# IR_repeater.net
KiCad netlist of a schematic drawn in EAGLE
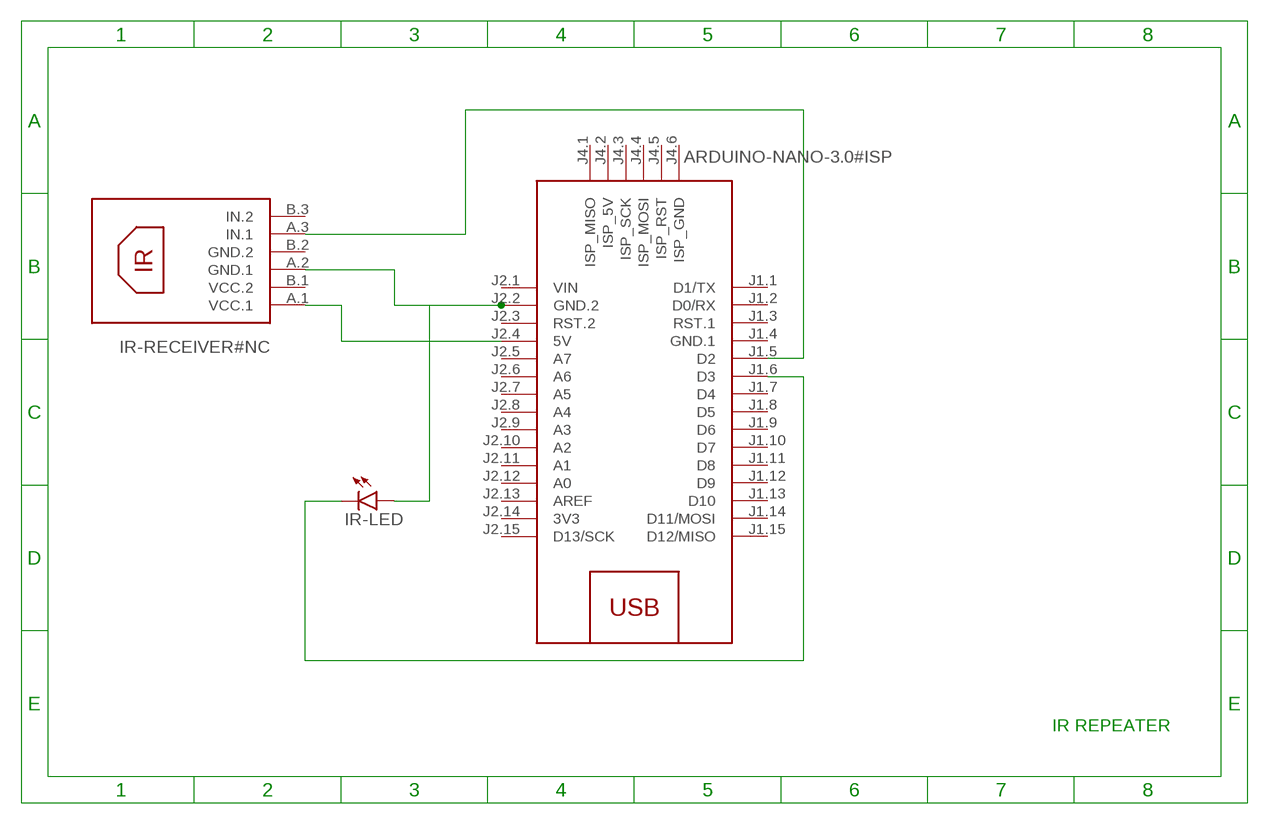
[diagram p0: schematic, sheet 1]

(export (version "E")
  (design (tool "Eeschema 10.0.6"))
  (components
    (comp (ref "IR-LED")
      (value "SFH482")
      (footprint "eagle-import:SFH482")
      (libsource (lib "eagle-import") (part "SFH482"))
    )
    (comp (ref "IR-RECEIVER")
      (value "IR-RECEIVER#NC")
      (footprint "eagle-import:IR-RECEIVER#NC")
      (libsource (lib "eagle-import") (part "IR-RECEIVER#NC"))
    )
    (comp (ref "M1")
      (value "ARDUINO-NANO-3.0#ISP")
      (footprint "eagle-import:ARDUINO-NANO-3.0#ISP")
      (libsource (lib "eagle-import") (part "ARDUINO-NANO-3.0#ISP"))
    )
  )
  (nets
    (net (code "1") (name "/3V3") (class "Default")
      (node (ref "M1") (pin "J2.14") (pinfunction "3V3_J2.14") (pintype "power_in"))
    )
    (net (code "2") (name "/GND.1") (class "Default")
      (node (ref "M1") (pin "J1.4") (pinfunction "GND.1_J1.4") (pintype "power_in"))
    )
    (net (code "3") (name "/VIN") (class "Default")
      (node (ref "M1") (pin "J2.1") (pinfunction "VIN_J2.1") (pintype "power_in"))
    )
    (net (code "4") (name "Net-(IR-LED-C)") (class "Default")
      (node (ref "IR-LED") (pin "K") (pinfunction "C_K") (pintype "passive"))
      (node (ref "M1") (pin "J1.6") (pinfunction "D3_J1.6") (pintype "bidirectional"))
    )
    (net (code "5") (name "Net-(IR-RECEIVER-GND.1)") (class "Default")
      (node (ref "IR-LED") (pin "A") (pinfunction "A_A") (pintype "passive"))
      (node (ref "IR-RECEIVER") (pin "A.2") (pinfunction "GND.1_A.2") (pintype "bidirectional"))
      (node (ref "M1") (pin "J2.2") (pinfunction "GND.2_J2.2") (pintype "power_in"))
    )
    (net (code "6") (name "Net-(IR-RECEIVER-IN.1)") (class "Default")
      (node (ref "IR-RECEIVER") (pin "A.3") (pinfunction "IN.1_A.3") (pintype "bidirectional"))
      (node (ref "M1") (pin "J1.5") (pinfunction "D2_J1.5") (pintype "bidirectional"))
    )
    (net (code "7") (name "Net-(IR-RECEIVER-VCC.1)") (class "Default")
      (node (ref "IR-RECEIVER") (pin "A.1") (pinfunction "VCC.1_A.1") (pintype "bidirectional"))
      (node (ref "M1") (pin "J2.4") (pinfunction "5V_J2.4") (pintype "power_in"))
    )
    (net (code "8") (name "unconnected-(IR-RECEIVER-GND.2-PadB.2)") (class "Default")
      (node (ref "IR-RECEIVER") (pin "B.2") (pinfunction "GND.2_B.2") (pintype "bidirectional"))
    )
    (net (code "9") (name "unconnected-(IR-RECEIVER-IN.2-PadB.3)") (class "Default")
      (node (ref "IR-RECEIVER") (pin "B.3") (pinfunction "IN.2_B.3") (pintype "bidirectional"))
    )
    (net (code "10") (name "unconnected-(IR-RECEIVER-VCC.2-PadB.1)") (class "Default")
      (node (ref "IR-RECEIVER") (pin "B.1") (pinfunction "VCC.2_B.1") (pintype "bidirectional"))
    )
    (net (code "11") (name "unconnected-(M1-A0-PadJ2.12)") (class "Default")
      (node (ref "M1") (pin "J2.12") (pinfunction "A0_J2.12") (pintype "bidirectional"))
    )
    (net (code "12") (name "unconnected-(M1-A1-PadJ2.11)") (class "Default")
      (node (ref "M1") (pin "J2.11") (pinfunction "A1_J2.11") (pintype "bidirectional"))
    )
    (net (code "13") (name "unconnected-(M1-A2-PadJ2.10)") (class "Default")
      (node (ref "M1") (pin "J2.10") (pinfunction "A2_J2.10") (pintype "bidirectional"))
    )
    (net (code "14") (name "unconnected-(M1-A3-PadJ2.9)") (class "Default")
      (node (ref "M1") (pin "J2.9") (pinfunction "A3_J2.9") (pintype "bidirectional"))
    )
    (net (code "15") (name "unconnected-(M1-A4-PadJ2.8)") (class "Default")
      (node (ref "M1") (pin "J2.8") (pinfunction "A4_J2.8") (pintype "bidirectional"))
    )
    (net (code "16") (name "unconnected-(M1-A5-PadJ2.7)") (class "Default")
      (node (ref "M1") (pin "J2.7") (pinfunction "A5_J2.7") (pintype "bidirectional"))
    )
    (net (code "17") (name "unconnected-(M1-A6-PadJ2.6)") (class "Default")
      (node (ref "M1") (pin "J2.6") (pinfunction "A6_J2.6") (pintype "bidirectional"))
    )
    (net (code "18") (name "unconnected-(M1-A7-PadJ2.5)") (class "Default")
      (node (ref "M1") (pin "J2.5") (pinfunction "A7_J2.5") (pintype "bidirectional"))
    )
    (net (code "19") (name "unconnected-(M1-AREF-PadJ2.13)") (class "Default")
      (node (ref "M1") (pin "J2.13") (pinfunction "AREF_J2.13") (pintype "bidirectional"))
    )
    (net (code "20") (name "unconnected-(M1-D0{slash}RX-PadJ1.2)") (class "Default")
      (node (ref "M1") (pin "J1.2") (pinfunction "D0/RX_J1.2") (pintype "bidirectional"))
    )
    (net (code "21") (name "unconnected-(M1-D1{slash}TX-PadJ1.1)") (class "Default")
      (node (ref "M1") (pin "J1.1") (pinfunction "D1/TX_J1.1") (pintype "bidirectional"))
    )
    (net (code "22") (name "unconnected-(M1-D4-PadJ1.7)") (class "Default")
      (node (ref "M1") (pin "J1.7") (pinfunction "D4_J1.7") (pintype "bidirectional"))
    )
    (net (code "23") (name "unconnected-(M1-D5-PadJ1.8)") (class "Default")
      (node (ref "M1") (pin "J1.8") (pinfunction "D5_J1.8") (pintype "bidirectional"))
    )
    (net (code "24") (name "unconnected-(M1-D6-PadJ1.9)") (class "Default")
      (node (ref "M1") (pin "J1.9") (pinfunction "D6_J1.9") (pintype "bidirectional"))
    )
    (net (code "25") (name "unconnected-(M1-D7-PadJ1.10)") (class "Default")
      (node (ref "M1") (pin "J1.10") (pinfunction "D7_J1.10") (pintype "bidirectional"))
    )
    (net (code "26") (name "unconnected-(M1-D8-PadJ1.11)") (class "Default")
      (node (ref "M1") (pin "J1.11") (pinfunction "D8_J1.11") (pintype "bidirectional"))
    )
    (net (code "27") (name "unconnected-(M1-D9-PadJ1.12)") (class "Default")
      (node (ref "M1") (pin "J1.12") (pinfunction "D9_J1.12") (pintype "bidirectional"))
    )
    (net (code "28") (name "unconnected-(M1-D10-PadJ1.13)") (class "Default")
      (node (ref "M1") (pin "J1.13") (pinfunction "D10_J1.13") (pintype "bidirectional"))
    )
    (net (code "29") (name "unconnected-(M1-D11{slash}MOSI-PadJ1.14)") (class "Default")
      (node (ref "M1") (pin "J1.14") (pinfunction "D11/MOSI_J1.14") (pintype "bidirectional"))
    )
    (net (code "30") (name "unconnected-(M1-D12{slash}MISO-PadJ1.15)") (class "Default")
      (node (ref "M1") (pin "J1.15") (pinfunction "D12/MISO_J1.15") (pintype "bidirectional"))
    )
    (net (code "31") (name "unconnected-(M1-D13{slash}SCK-PadJ2.15)") (class "Default")
      (node (ref "M1") (pin "J2.15") (pinfunction "D13/SCK_J2.15") (pintype "bidirectional"))
    )
    (net (code "32") (name "unconnected-(M1-ISP_5V-PadJ4.2)") (class "Default")
      (node (ref "M1") (pin "J4.2") (pinfunction "ISP_5V_J4.2") (pintype "bidirectional"))
    )
    (net (code "33") (name "unconnected-(M1-ISP_GND-PadJ4.6)") (class "Default")
      (node (ref "M1") (pin "J4.6") (pinfunction "ISP_GND_J4.6") (pintype "bidirectional"))
    )
    (net (code "34") (name "unconnected-(M1-ISP_MISO-PadJ4.1)") (class "Default")
      (node (ref "M1") (pin "J4.1") (pinfunction "ISP_MISO_J4.1") (pintype "bidirectional"))
    )
    (net (code "35") (name "unconnected-(M1-ISP_MOSI-PadJ4.4)") (class "Default")
      (node (ref "M1") (pin "J4.4") (pinfunction "ISP_MOSI_J4.4") (pintype "bidirectional"))
    )
    (net (code "36") (name "unconnected-(M1-ISP_RST-PadJ4.5)") (class "Default")
      (node (ref "M1") (pin "J4.5") (pinfunction "ISP_RST_J4.5") (pintype "bidirectional"))
    )
    (net (code "37") (name "unconnected-(M1-ISP_SCK-PadJ4.3)") (class "Default")
      (node (ref "M1") (pin "J4.3") (pinfunction "ISP_SCK_J4.3") (pintype "bidirectional"))
    )
    (net (code "38") (name "unconnected-(M1-RST.1-PadJ1.3)") (class "Default")
      (node (ref "M1") (pin "J1.3") (pinfunction "RST.1_J1.3") (pintype "bidirectional"))
    )
    (net (code "39") (name "unconnected-(M1-RST.2-PadJ2.3)") (class "Default")
      (node (ref "M1") (pin "J2.3") (pinfunction "RST.2_J2.3") (pintype "bidirectional"))
    )
  )
)
